# base-1.net
KiCad netlist of a schematic drawn in EAGLE
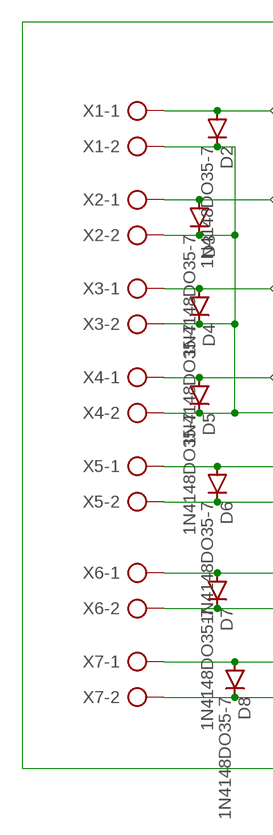
[diagram p0: schematic, sheet 1, part 1 of 2]
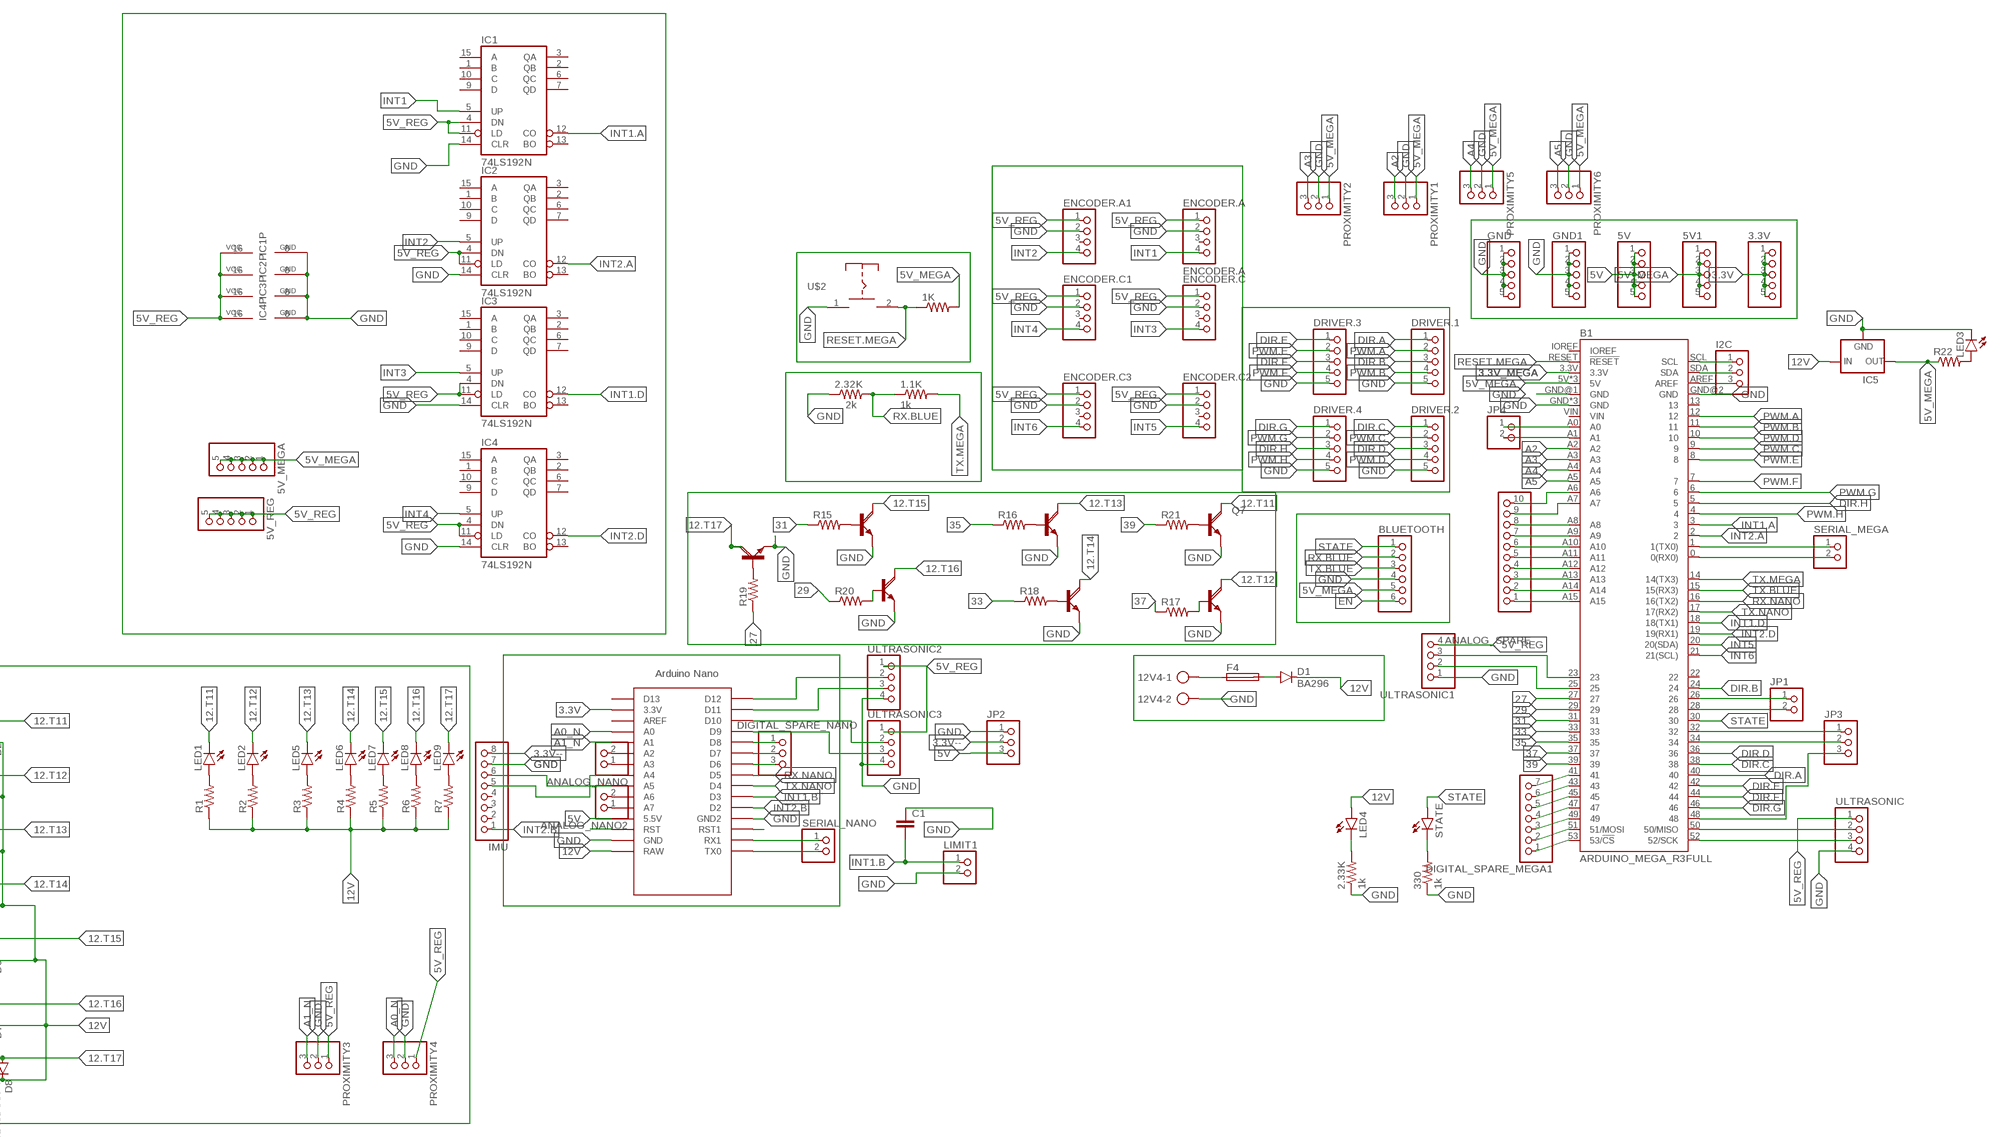
[diagram p1: schematic, sheet 1, part 2 of 2]

(export (version "E")
  (design (tool "Eeschema 10.0.6"))
  (components
    (comp (ref "1.1K")
      (value "1k")
      (footprint "eagle-import:0204_5")
      (libsource (lib "eagle-import") (part "R-US_0204/5"))
    )
    (comp (ref "1K")
      (value "R-US_0204/5")
      (footprint "eagle-import:0204_5")
      (libsource (lib "eagle-import") (part "R-US_0204/5"))
    )
    (comp (ref "2.32K")
      (value "2k")
      (footprint "eagle-import:0204_5")
      (libsource (lib "eagle-import") (part "R-US_0204/5"))
    )
    (comp (ref "2.33K")
      (value "1k")
      (footprint "eagle-import:0207_10")
      (libsource (lib "eagle-import") (part "R-US_0207/10"))
    )
    (comp (ref "3.3V")
      (value "PINHD-1X5")
      (footprint "eagle-import:1X05")
      (libsource (lib "eagle-import") (part "PINHD-1X5"))
    )
    (comp (ref "5V")
      (value "PINHD-1X5")
      (footprint "eagle-import:1X05")
      (libsource (lib "eagle-import") (part "PINHD-1X5"))
    )
    (comp (ref "5V1")
      (value "PINHD-1X5")
      (footprint "eagle-import:1X05")
      (libsource (lib "eagle-import") (part "PINHD-1X5"))
    )
    (comp (ref "5V_MEGA")
      (value "PINHD-1X5")
      (footprint "eagle-import:1X05")
      (libsource (lib "eagle-import") (part "PINHD-1X5"))
    )
    (comp (ref "5V_REG")
      (value "PINHD-1X5")
      (footprint "eagle-import:1X05")
      (libsource (lib "eagle-import") (part "PINHD-1X5"))
    )
    (comp (ref "12V4")
      (value "W237-113")
      (footprint "eagle-import:W237-113")
      (libsource (lib "eagle-import") (part "W237-113"))
    )
    (comp (ref "330")
      (value "1k")
      (footprint "eagle-import:0204_5")
      (libsource (lib "eagle-import") (part "R-US_0204/5"))
    )
    (comp (ref "ANALOG_NANO")
      (value "PINHD-1X2")
      (footprint "eagle-import:1X02")
      (libsource (lib "eagle-import") (part "PINHD-1X2"))
    )
    (comp (ref "ANALOG_NANO2")
      (value "PINHD-1X2")
      (footprint "eagle-import:1X02")
      (libsource (lib "eagle-import") (part "PINHD-1X2"))
    )
    (comp (ref "ANALOG_SPARE")
      (value "PINHD-1X10")
      (footprint "eagle-import:1X10")
      (libsource (lib "eagle-import") (part "PINHD-1X10"))
    )
    (comp (ref "B1")
      (value "ARDUINO_MEGA_R3FULL")
      (footprint "eagle-import:ARDUINO_MEGA_NO_SILK")
      (libsource (lib "eagle-import") (part "ARDUINO_MEGA_R3FULL"))
    )
    (comp (ref "BLUETOOTH")
      (value "PINHD-1X6")
      (footprint "eagle-import:1X06")
      (libsource (lib "eagle-import") (part "PINHD-1X6"))
    )
    (comp (ref "C1")
      (value "C-EU025-025X050")
      (footprint "eagle-import:C025-025X050")
      (libsource (lib "eagle-import") (part "C-EU025-025X050"))
    )
    (comp (ref "D1")
      (value "BA296")
      (footprint "eagle-import:P2-15")
      (libsource (lib "eagle-import") (part "BA296"))
    )
    (comp (ref "D2")
      (value "1N4148DO35-7")
      (footprint "eagle-import:DO35-7")
      (libsource (lib "eagle-import") (part "1N4148DO35-7"))
    )
    (comp (ref "D3")
      (value "1N4148DO35-7")
      (footprint "eagle-import:DO35-7")
      (libsource (lib "eagle-import") (part "1N4148DO35-7"))
    )
    (comp (ref "D4")
      (value "1N4148DO35-7")
      (footprint "eagle-import:DO35-7")
      (libsource (lib "eagle-import") (part "1N4148DO35-7"))
    )
    (comp (ref "D5")
      (value "1N4148DO35-7")
      (footprint "eagle-import:DO35-7")
      (libsource (lib "eagle-import") (part "1N4148DO35-7"))
    )
    (comp (ref "D6")
      (value "1N4148DO35-7")
      (footprint "eagle-import:DO35-7")
      (libsource (lib "eagle-import") (part "1N4148DO35-7"))
    )
    (comp (ref "D7")
      (value "1N4148DO35-7")
      (footprint "eagle-import:DO35-7")
      (libsource (lib "eagle-import") (part "1N4148DO35-7"))
    )
    (comp (ref "D8")
      (value "1N4148DO35-7")
      (footprint "eagle-import:DO35-7")
      (libsource (lib "eagle-import") (part "1N4148DO35-7"))
    )
    (comp (ref "DIGITAL_SPARE_MEGA1")
      (value "PINHD-1X7")
      (footprint "eagle-import:1X07")
      (libsource (lib "eagle-import") (part "PINHD-1X7"))
    )
    (comp (ref "DIGITAL_SPARE_NANO")
      (value "PINHD-1X3")
      (footprint "eagle-import:1X03")
      (libsource (lib "eagle-import") (part "PINHD-1X3"))
    )
    (comp (ref "DRIVER.1")
      (value "PINHD-1X5")
      (footprint "eagle-import:1X05")
      (libsource (lib "eagle-import") (part "PINHD-1X5"))
    )
    (comp (ref "DRIVER.2")
      (value "PINHD-1X5")
      (footprint "eagle-import:1X05")
      (libsource (lib "eagle-import") (part "PINHD-1X5"))
    )
    (comp (ref "DRIVER.3")
      (value "PINHD-1X5")
      (footprint "eagle-import:1X05")
      (libsource (lib "eagle-import") (part "PINHD-1X5"))
    )
    (comp (ref "DRIVER.4")
      (value "PINHD-1X5")
      (footprint "eagle-import:1X05")
      (libsource (lib "eagle-import") (part "PINHD-1X5"))
    )
    (comp (ref "ENCODER.A")
      (value "ENCODER.A")
      (footprint "eagle-import:1X04")
      (libsource (lib "eagle-import") (part "PINHD-1X4"))
    )
    (comp (ref "ENCODER.A1")
      (value "PINHD-1X4")
      (footprint "eagle-import:1X04")
      (libsource (lib "eagle-import") (part "PINHD-1X4"))
    )
    (comp (ref "ENCODER.C")
      (value "PINHD-1X4")
      (footprint "eagle-import:1X04")
      (libsource (lib "eagle-import") (part "PINHD-1X4"))
    )
    (comp (ref "ENCODER.C1")
      (value "PINHD-1X4")
      (footprint "eagle-import:1X04")
      (libsource (lib "eagle-import") (part "PINHD-1X4"))
    )
    (comp (ref "ENCODER.C2")
      (value "PINHD-1X4")
      (footprint "eagle-import:1X04")
      (libsource (lib "eagle-import") (part "PINHD-1X4"))
    )
    (comp (ref "ENCODER.C3")
      (value "PINHD-1X4")
      (footprint "eagle-import:1X04")
      (libsource (lib "eagle-import") (part "PINHD-1X4"))
    )
    (comp (ref "F4")
      (value "SH22,5A")
      (footprint "eagle-import:SH22,5A")
      (fields (field (name "MPN") "0031.7701.11"))
      (libsource (lib "eagle-import") (part "SH22,5A"))
    )
    (comp (ref "GND")
      (value "PINHD-1X5")
      (footprint "eagle-import:1X05")
      (libsource (lib "eagle-import") (part "PINHD-1X5"))
    )
    (comp (ref "GND1")
      (value "PINHD-1X5")
      (footprint "eagle-import:1X05")
      (libsource (lib "eagle-import") (part "PINHD-1X5"))
    )
    (comp (ref "I2C")
      (value "PINHD-1X3")
      (footprint "eagle-import:1X03")
      (libsource (lib "eagle-import") (part "PINHD-1X3"))
    )
    (comp (ref "IC1")
      (value "74LS192N")
      (footprint "eagle-import:DIL16")
      (libsource (lib "eagle-import") (part "74192NLS"))
    )
    (comp (ref "IC2")
      (value "74LS192N")
      (footprint "eagle-import:DIL16")
      (libsource (lib "eagle-import") (part "74192NLS"))
    )
    (comp (ref "IC3")
      (value "74LS192N")
      (footprint "eagle-import:DIL16")
      (libsource (lib "eagle-import") (part "74192NLS"))
    )
    (comp (ref "IC4")
      (value "74LS192N")
      (footprint "eagle-import:DIL16")
      (libsource (lib "eagle-import") (part "74192NLS"))
    )
    (comp (ref "IC5")
      (value "79XX-TO3")
      (footprint "eagle-import:TO3-79")
      (libsource (lib "eagle-import") (part "79XX-TO3"))
    )
    (comp (ref "IMU")
      (value "PINHD-1X8")
      (footprint "eagle-import:1X08")
      (libsource (lib "eagle-import") (part "PINHD-1X8"))
    )
    (comp (ref "JP1")
      (value "PINHD-1X2")
      (footprint "eagle-import:1X02")
      (libsource (lib "eagle-import") (part "PINHD-1X2"))
    )
    (comp (ref "JP2")
      (value "PINHD-1X3")
      (footprint "eagle-import:1X03")
      (libsource (lib "eagle-import") (part "PINHD-1X3"))
    )
    (comp (ref "JP3")
      (value "PINHD-1X3")
      (footprint "eagle-import:1X03")
      (libsource (lib "eagle-import") (part "PINHD-1X3"))
    )
    (comp (ref "JP4")
      (value "PINHD-1X2")
      (footprint "eagle-import:1X02")
      (libsource (lib "eagle-import") (part "PINHD-1X2"))
    )
    (comp (ref "LED1")
      (value "LED3MM")
      (footprint "eagle-import:LED3MM")
      (libsource (lib "eagle-import") (part "LED3MM"))
    )
    (comp (ref "LED2")
      (value "LED3MM")
      (footprint "eagle-import:LED3MM")
      (libsource (lib "eagle-import") (part "LED3MM"))
    )
    (comp (ref "LED3")
      (value "LED3MM")
      (footprint "eagle-import:LED3MM")
      (libsource (lib "eagle-import") (part "LED3MM"))
    )
    (comp (ref "LED4")
      (value "LED5MM")
      (footprint "eagle-import:LED5MM")
      (libsource (lib "eagle-import") (part "LED5MM"))
    )
    (comp (ref "LED5")
      (value "LED3MM")
      (footprint "eagle-import:LED3MM")
      (libsource (lib "eagle-import") (part "LED3MM"))
    )
    (comp (ref "LED6")
      (value "LED3MM")
      (footprint "eagle-import:LED3MM")
      (libsource (lib "eagle-import") (part "LED3MM"))
    )
    (comp (ref "LED7")
      (value "LED3MM")
      (footprint "eagle-import:LED3MM")
      (libsource (lib "eagle-import") (part "LED3MM"))
    )
    (comp (ref "LED8")
      (value "LED3MM")
      (footprint "eagle-import:LED3MM")
      (libsource (lib "eagle-import") (part "LED3MM"))
    )
    (comp (ref "LED9")
      (value "LED3MM")
      (footprint "eagle-import:LED3MM")
      (libsource (lib "eagle-import") (part "LED3MM"))
    )
    (comp (ref "LIMIT1")
      (value "PINHD-1X2")
      (footprint "eagle-import:1X02")
      (libsource (lib "eagle-import") (part "PINHD-1X2"))
    )
    (comp (ref "PROXIMITY1")
      (value "PINHD-1X3")
      (footprint "eagle-import:1X03")
      (libsource (lib "eagle-import") (part "PINHD-1X3"))
    )
    (comp (ref "PROXIMITY2")
      (value "PINHD-1X3")
      (footprint "eagle-import:1X03")
      (libsource (lib "eagle-import") (part "PINHD-1X3"))
    )
    (comp (ref "PROXIMITY3")
      (value "PINHD-1X3")
      (footprint "eagle-import:1X03")
      (libsource (lib "eagle-import") (part "PINHD-1X3"))
    )
    (comp (ref "PROXIMITY4")
      (value "PINHD-1X3")
      (footprint "eagle-import:1X03")
      (libsource (lib "eagle-import") (part "PINHD-1X3"))
    )
    (comp (ref "PROXIMITY5")
      (value "PINHD-1X3")
      (footprint "eagle-import:1X03")
      (libsource (lib "eagle-import") (part "PINHD-1X3"))
    )
    (comp (ref "PROXIMITY6")
      (value "PINHD-1X3")
      (footprint "eagle-import:1X03")
      (libsource (lib "eagle-import") (part "PINHD-1X3"))
    )
    (comp (ref "Q1")
      (value "TIP120")
      (footprint "eagle-import:TO220AV")
      (libsource (lib "eagle-import") (part "TIP120"))
    )
    (comp (ref "Q2")
      (value "TIP120")
      (footprint "eagle-import:TO220AV")
      (libsource (lib "eagle-import") (part "TIP120"))
    )
    (comp (ref "Q3")
      (value "TIP120")
      (footprint "eagle-import:TO220AV")
      (libsource (lib "eagle-import") (part "TIP120"))
    )
    (comp (ref "Q4")
      (value "TIP120")
      (footprint "eagle-import:TO220AV")
      (libsource (lib "eagle-import") (part "TIP120"))
    )
    (comp (ref "Q5")
      (value "TIP120")
      (footprint "eagle-import:TO220AV")
      (libsource (lib "eagle-import") (part "TIP120"))
    )
    (comp (ref "Q6")
      (value "TIP120")
      (footprint "eagle-import:TO220AV")
      (libsource (lib "eagle-import") (part "TIP120"))
    )
    (comp (ref "Q7")
      (value "TIP120")
      (footprint "eagle-import:TO220AV")
      (libsource (lib "eagle-import") (part "TIP120"))
    )
    (comp (ref "R1")
      (value "R-US_0204/5")
      (footprint "eagle-import:0204_5")
      (libsource (lib "eagle-import") (part "R-US_0204/5"))
    )
    (comp (ref "R2")
      (value "R-US_0204/5")
      (footprint "eagle-import:0204_5")
      (libsource (lib "eagle-import") (part "R-US_0204/5"))
    )
    (comp (ref "R3")
      (value "R-US_0204/5")
      (footprint "eagle-import:0204_5")
      (libsource (lib "eagle-import") (part "R-US_0204/5"))
    )
    (comp (ref "R4")
      (value "R-US_0204/5")
      (footprint "eagle-import:0204_5")
      (libsource (lib "eagle-import") (part "R-US_0204/5"))
    )
    (comp (ref "R5")
      (value "R-US_0204/5")
      (footprint "eagle-import:0204_5")
      (libsource (lib "eagle-import") (part "R-US_0204/5"))
    )
    (comp (ref "R6")
      (value "R-US_0204/5")
      (footprint "eagle-import:0204_5")
      (libsource (lib "eagle-import") (part "R-US_0204/5"))
    )
    (comp (ref "R7")
      (value "R-US_0204/5")
      (footprint "eagle-import:0204_5")
      (libsource (lib "eagle-import") (part "R-US_0204/5"))
    )
    (comp (ref "R15")
      (value "R-US_0207/10")
      (footprint "eagle-import:0207_10")
      (libsource (lib "eagle-import") (part "R-US_0207/10"))
    )
    (comp (ref "R16")
      (value "R-US_0204/7")
      (footprint "eagle-import:0204_7")
      (libsource (lib "eagle-import") (part "R-US_0204/7"))
    )
    (comp (ref "R17")
      (value "R-US_0204/7")
      (footprint "eagle-import:0204_7")
      (libsource (lib "eagle-import") (part "R-US_0204/7"))
    )
    (comp (ref "R18")
      (value "R-US_0204/7")
      (footprint "eagle-import:0204_7")
      (libsource (lib "eagle-import") (part "R-US_0204/7"))
    )
    (comp (ref "R19")
      (value "R-US_0204/7")
      (footprint "eagle-import:0204_7")
      (libsource (lib "eagle-import") (part "R-US_0204/7"))
    )
    (comp (ref "R20")
      (value "R-US_0204/7")
      (footprint "eagle-import:0204_7")
      (libsource (lib "eagle-import") (part "R-US_0204/7"))
    )
    (comp (ref "R21")
      (value "R-US_0204/5")
      (footprint "eagle-import:0204_5")
      (libsource (lib "eagle-import") (part "R-US_0204/5"))
    )
    (comp (ref "R22")
      (value "R-US_0204/5")
      (footprint "eagle-import:0204_5")
      (libsource (lib "eagle-import") (part "R-US_0204/5"))
    )
    (comp (ref "SERIAL_MEGA")
      (value "PINHD-1X2")
      (footprint "eagle-import:1X02")
      (libsource (lib "eagle-import") (part "PINHD-1X2"))
    )
    (comp (ref "SERIAL_NANO")
      (value "PINHD-1X2")
      (footprint "eagle-import:1X02")
      (libsource (lib "eagle-import") (part "PINHD-1X2"))
    )
    (comp (ref "STATE")
      (value "LED3MM")
      (footprint "eagle-import:LED3MM")
      (libsource (lib "eagle-import") (part "LED3MM"))
    )
    (comp (ref "U$1")
      (value "NANO")
      (footprint "eagle-import:NANO")
      (libsource (lib "eagle-import") (part "NANO"))
    )
    (comp (ref "U$2")
      (value "PUSHBOTTON")
      (footprint "eagle-import:PUSHBOTTON")
      (libsource (lib "eagle-import") (part "PUSHBOTTON"))
    )
    (comp (ref "ULTRASONIC")
      (value "PINHD-1X4")
      (footprint "eagle-import:1X04")
      (libsource (lib "eagle-import") (part "PINHD-1X4"))
    )
    (comp (ref "ULTRASONIC1")
      (value "PINHD-1X4")
      (footprint "eagle-import:1X04")
      (libsource (lib "eagle-import") (part "PINHD-1X4"))
    )
    (comp (ref "ULTRASONIC2")
      (value "PINHD-1X4")
      (footprint "eagle-import:1X04")
      (libsource (lib "eagle-import") (part "PINHD-1X4"))
    )
    (comp (ref "ULTRASONIC3")
      (value "PINHD-1X4")
      (footprint "eagle-import:1X04")
      (libsource (lib "eagle-import") (part "PINHD-1X4"))
    )
    (comp (ref "X1")
      (value "AK300/2")
      (footprint "eagle-import:AK300_2")
      (libsource (lib "eagle-import") (part "AK300/2"))
    )
    (comp (ref "X2")
      (value "AK300/2")
      (footprint "eagle-import:AK300_2")
      (libsource (lib "eagle-import") (part "AK300/2"))
    )
    (comp (ref "X3")
      (value "AK300/2")
      (footprint "eagle-import:AK300_2")
      (libsource (lib "eagle-import") (part "AK300/2"))
    )
    (comp (ref "X4")
      (value "AK300/2")
      (footprint "eagle-import:AK300_2")
      (libsource (lib "eagle-import") (part "AK300/2"))
    )
    (comp (ref "X5")
      (value "AK300/2")
      (footprint "eagle-import:AK300_2")
      (libsource (lib "eagle-import") (part "AK300/2"))
    )
    (comp (ref "X6")
      (value "AK300/2")
      (footprint "eagle-import:AK300_2")
      (libsource (lib "eagle-import") (part "AK300/2"))
    )
    (comp (ref "X7")
      (value "AK300/2")
      (footprint "eagle-import:AK300_2")
      (libsource (lib "eagle-import") (part "AK300/2"))
    )
  )
  (nets
    (net (code "1") (name "3.3V") (class "Default")
      (node (ref "3.3V") (pin "1") (pinfunction "1_1") (pintype "passive"))
      (node (ref "3.3V") (pin "2") (pinfunction "2_2") (pintype "passive"))
      (node (ref "3.3V") (pin "3") (pinfunction "3_3") (pintype "passive"))
      (node (ref "3.3V") (pin "4") (pinfunction "4_4") (pintype "passive"))
      (node (ref "3.3V") (pin "5") (pinfunction "5_5") (pintype "passive"))
      (node (ref "U$1") (pin "3.3V") (pinfunction "3.3V_3.3V") (pintype "bidirectional"))
    )
    (net (code "2") (name "3.3V--") (class "Default")
      (node (ref "IMU") (pin "8") (pinfunction "8_8") (pintype "passive"))
      (node (ref "JP2") (pin "2") (pinfunction "2_2") (pintype "passive"))
    )
    (net (code "3") (name "3.3V_MEGA") (class "Default")
      (node (ref "B1") (pin "3.3V") (pinfunction "3.3V_3.3V") (pintype "bidirectional"))
    )
    (net (code "4") (name "5V") (class "Default")
      (node (ref "5V") (pin "1") (pinfunction "1_1") (pintype "passive"))
      (node (ref "5V") (pin "2") (pinfunction "2_2") (pintype "passive"))
      (node (ref "5V") (pin "3") (pinfunction "3_3") (pintype "passive"))
      (node (ref "5V") (pin "4") (pinfunction "4_4") (pintype "passive"))
      (node (ref "5V") (pin "5") (pinfunction "5_5") (pintype "passive"))
      (node (ref "JP2") (pin "3") (pinfunction "3_3") (pintype "passive"))
      (node (ref "U$1") (pin "5V") (pinfunction "5.5V_5V") (pintype "bidirectional"))
    )
    (net (code "5") (name "5V_MEGA") (class "Default")
      (node (ref "1K") (pin "2") (pinfunction "2_2") (pintype "passive"))
      (node (ref "5V1") (pin "1") (pinfunction "1_1") (pintype "passive"))
      (node (ref "5V1") (pin "2") (pinfunction "2_2") (pintype "passive"))
      (node (ref "5V1") (pin "3") (pinfunction "3_3") (pintype "passive"))
      (node (ref "5V1") (pin "4") (pinfunction "4_4") (pintype "passive"))
      (node (ref "5V1") (pin "5") (pinfunction "5_5") (pintype "passive"))
      (node (ref "5V_MEGA") (pin "1") (pinfunction "1_1") (pintype "passive"))
      (node (ref "5V_MEGA") (pin "2") (pinfunction "2_2") (pintype "passive"))
      (node (ref "5V_MEGA") (pin "3") (pinfunction "3_3") (pintype "passive"))
      (node (ref "5V_MEGA") (pin "4") (pinfunction "4_4") (pintype "passive"))
      (node (ref "5V_MEGA") (pin "5") (pinfunction "5_5") (pintype "passive"))
      (node (ref "B1") (pin "5V") (pinfunction "5V_5V") (pintype "bidirectional"))
      (node (ref "B1") (pin "5V@1") (pinfunction "5V_5V@1") (pintype "bidirectional"))
      (node (ref "B1") (pin "5V@2") (pinfunction "5V_5V@2") (pintype "bidirectional"))
      (node (ref "BLUETOOTH") (pin "5") (pinfunction "5_5") (pintype "passive"))
      (node (ref "IC5") (pin "1") (pinfunction "OUT_1") (pintype "passive"))
      (node (ref "PROXIMITY1") (pin "1") (pinfunction "1_1") (pintype "passive"))
      (node (ref "PROXIMITY2") (pin "1") (pinfunction "1_1") (pintype "passive"))
      (node (ref "PROXIMITY5") (pin "1") (pinfunction "1_1") (pintype "passive"))
      (node (ref "PROXIMITY6") (pin "1") (pinfunction "1_1") (pintype "passive"))
      (node (ref "R22") (pin "1") (pinfunction "1_1") (pintype "passive"))
    )
    (net (code "6") (name "5V_REG") (class "Default")
      (node (ref "5V_REG") (pin "1") (pinfunction "1_1") (pintype "passive"))
      (node (ref "5V_REG") (pin "2") (pinfunction "2_2") (pintype "passive"))
      (node (ref "5V_REG") (pin "3") (pinfunction "3_3") (pintype "passive"))
      (node (ref "5V_REG") (pin "4") (pinfunction "4_4") (pintype "passive"))
      (node (ref "5V_REG") (pin "5") (pinfunction "5_5") (pintype "passive"))
      (node (ref "ENCODER.A") (pin "1") (pinfunction "1_1") (pintype "passive"))
      (node (ref "ENCODER.A1") (pin "1") (pinfunction "1_1") (pintype "passive"))
      (node (ref "ENCODER.C") (pin "1") (pinfunction "1_1") (pintype "passive"))
      (node (ref "ENCODER.C1") (pin "1") (pinfunction "1_1") (pintype "passive"))
      (node (ref "ENCODER.C2") (pin "1") (pinfunction "1_1") (pintype "passive"))
      (node (ref "ENCODER.C3") (pin "1") (pinfunction "1_1") (pintype "passive"))
      (node (ref "IC1") (pin "11") (pinfunction "LD_11") (pintype "input"))
      (node (ref "IC1") (pin "16") (pinfunction "VCC_16") (pintype "power_in"))
      (node (ref "IC1") (pin "4") (pinfunction "DN_4") (pintype "input"))
      (node (ref "IC2") (pin "11") (pinfunction "LD_11") (pintype "input"))
      (node (ref "IC2") (pin "16") (pinfunction "VCC_16") (pintype "power_in"))
      (node (ref "IC2") (pin "4") (pinfunction "DN_4") (pintype "input"))
      (node (ref "IC3") (pin "11") (pinfunction "LD_11") (pintype "input"))
      (node (ref "IC3") (pin "16") (pinfunction "VCC_16") (pintype "power_in"))
      (node (ref "IC3") (pin "4") (pinfunction "DN_4") (pintype "input"))
      (node (ref "IC4") (pin "11") (pinfunction "LD_11") (pintype "input"))
      (node (ref "IC4") (pin "16") (pinfunction "VCC_16") (pintype "power_in"))
      (node (ref "IC4") (pin "4") (pinfunction "DN_4") (pintype "input"))
      (node (ref "PROXIMITY3") (pin "1") (pinfunction "1_1") (pintype "passive"))
      (node (ref "PROXIMITY4") (pin "1") (pinfunction "1_1") (pintype "passive"))
      (node (ref "ULTRASONIC") (pin "1") (pinfunction "1_1") (pintype "passive"))
      (node (ref "ULTRASONIC1") (pin "4") (pinfunction "4_4") (pintype "passive"))
      (node (ref "ULTRASONIC2") (pin "1") (pinfunction "1_1") (pintype "passive"))
      (node (ref "ULTRASONIC3") (pin "1") (pinfunction "1_1") (pintype "passive"))
    )
    (net (code "7") (name "12.T11") (class "Default")
      (node (ref "D2") (pin "A") (pinfunction "A_A") (pintype "passive"))
      (node (ref "LED1") (pin "K") (pinfunction "C_K") (pintype "passive"))
      (node (ref "Q7") (pin "C") (pinfunction "C_C") (pintype "passive"))
      (node (ref "X1") (pin "1") (pinfunction "KL_1") (pintype "passive"))
    )
    (net (code "8") (name "12.T12") (class "Default")
      (node (ref "D3") (pin "A") (pinfunction "A_A") (pintype "passive"))
      (node (ref "LED2") (pin "K") (pinfunction "C_K") (pintype "passive"))
      (node (ref "Q5") (pin "C") (pinfunction "C_C") (pintype "passive"))
      (node (ref "X2") (pin "1") (pinfunction "KL_1") (pintype "passive"))
    )
    (net (code "9") (name "12.T13") (class "Default")
      (node (ref "D4") (pin "A") (pinfunction "A_A") (pintype "passive"))
      (node (ref "LED5") (pin "K") (pinfunction "C_K") (pintype "passive"))
      (node (ref "Q2") (pin "C") (pinfunction "C_C") (pintype "passive"))
      (node (ref "X3") (pin "1") (pinfunction "KL_1") (pintype "passive"))
    )
    (net (code "10") (name "12.T14") (class "Default")
      (node (ref "D5") (pin "A") (pinfunction "A_A") (pintype "passive"))
      (node (ref "LED6") (pin "K") (pinfunction "C_K") (pintype "passive"))
      (node (ref "Q4") (pin "C") (pinfunction "C_C") (pintype "passive"))
      (node (ref "X4") (pin "1") (pinfunction "KL_1") (pintype "passive"))
    )
    (net (code "11") (name "12.T15") (class "Default")
      (node (ref "D6") (pin "A") (pinfunction "A_A") (pintype "passive"))
      (node (ref "LED7") (pin "K") (pinfunction "C_K") (pintype "passive"))
      (node (ref "Q1") (pin "C") (pinfunction "C_C") (pintype "passive"))
      (node (ref "X5") (pin "1") (pinfunction "KL_1") (pintype "passive"))
    )
    (net (code "12") (name "12.T16") (class "Default")
      (node (ref "D7") (pin "A") (pinfunction "A_A") (pintype "passive"))
      (node (ref "LED8") (pin "K") (pinfunction "C_K") (pintype "passive"))
      (node (ref "Q6") (pin "C") (pinfunction "C_C") (pintype "passive"))
      (node (ref "X6") (pin "1") (pinfunction "KL_1") (pintype "passive"))
    )
    (net (code "13") (name "12.T17") (class "Default")
      (node (ref "D8") (pin "A") (pinfunction "A_A") (pintype "passive"))
      (node (ref "LED9") (pin "K") (pinfunction "C_K") (pintype "passive"))
      (node (ref "Q3") (pin "C") (pinfunction "C_C") (pintype "passive"))
      (node (ref "X7") (pin "1") (pinfunction "KL_1") (pintype "passive"))
    )
    (net (code "14") (name "12V") (class "Default")
      (node (ref "D1") (pin "C") (pinfunction "C_C") (pintype "passive"))
      (node (ref "D2") (pin "C") (pinfunction "C_C") (pintype "passive"))
      (node (ref "D3") (pin "C") (pinfunction "C_C") (pintype "passive"))
      (node (ref "D4") (pin "C") (pinfunction "C_C") (pintype "passive"))
      (node (ref "D5") (pin "C") (pinfunction "C_C") (pintype "passive"))
      (node (ref "D6") (pin "C") (pinfunction "C_C") (pintype "passive"))
      (node (ref "D7") (pin "C") (pinfunction "C_C") (pintype "passive"))
      (node (ref "D8") (pin "C") (pinfunction "C_C") (pintype "passive"))
      (node (ref "IC5") (pin "3") (pinfunction "IN_3") (pintype "input"))
      (node (ref "LED4") (pin "A") (pinfunction "A_A") (pintype "passive"))
      (node (ref "R1") (pin "1") (pinfunction "1_1") (pintype "passive"))
      (node (ref "R2") (pin "1") (pinfunction "1_1") (pintype "passive"))
      (node (ref "R3") (pin "1") (pinfunction "1_1") (pintype "passive"))
      (node (ref "R4") (pin "1") (pinfunction "1_1") (pintype "passive"))
      (node (ref "R5") (pin "1") (pinfunction "1_1") (pintype "passive"))
      (node (ref "R6") (pin "1") (pinfunction "1_1") (pintype "passive"))
      (node (ref "R7") (pin "1") (pinfunction "1_1") (pintype "passive"))
      (node (ref "U$1") (pin "RAW") (pinfunction "RAW_RAW") (pintype "bidirectional"))
      (node (ref "X1") (pin "2") (pinfunction "KL_2") (pintype "passive"))
      (node (ref "X2") (pin "2") (pinfunction "KL_2") (pintype "passive"))
      (node (ref "X3") (pin "2") (pinfunction "KL_2") (pintype "passive"))
      (node (ref "X4") (pin "2") (pinfunction "KL_2") (pintype "passive"))
      (node (ref "X5") (pin "2") (pinfunction "KL_2") (pintype "passive"))
      (node (ref "X6") (pin "2") (pinfunction "KL_2") (pintype "passive"))
      (node (ref "X7") (pin "2") (pinfunction "KL_2") (pintype "passive"))
    )
    (net (code "15") (name "27") (class "Default")
      (node (ref "B1") (pin "27") (pinfunction "27_27") (pintype "bidirectional"))
      (node (ref "R19") (pin "1") (pinfunction "1_1") (pintype "passive"))
    )
    (net (code "16") (name "29") (class "Default")
      (node (ref "B1") (pin "29") (pinfunction "29_29") (pintype "bidirectional"))
      (node (ref "R20") (pin "1") (pinfunction "1_1") (pintype "passive"))
    )
    (net (code "17") (name "31") (class "Default")
      (node (ref "B1") (pin "31") (pinfunction "31_31") (pintype "bidirectional"))
      (node (ref "R15") (pin "1") (pinfunction "1_1") (pintype "passive"))
    )
    (net (code "18") (name "33") (class "Default")
      (node (ref "B1") (pin "33") (pinfunction "33_33") (pintype "bidirectional"))
      (node (ref "R18") (pin "1") (pinfunction "1_1") (pintype "passive"))
    )
    (net (code "19") (name "35") (class "Default")
      (node (ref "B1") (pin "35") (pinfunction "35_35") (pintype "bidirectional"))
      (node (ref "R16") (pin "1") (pinfunction "1_1") (pintype "passive"))
    )
    (net (code "20") (name "37") (class "Default")
      (node (ref "B1") (pin "37") (pinfunction "37_37") (pintype "bidirectional"))
      (node (ref "R17") (pin "1") (pinfunction "1_1") (pintype "passive"))
    )
    (net (code "21") (name "39") (class "Default")
      (node (ref "B1") (pin "39") (pinfunction "39_39") (pintype "bidirectional"))
      (node (ref "R21") (pin "1") (pinfunction "1_1") (pintype "passive"))
    )
    (net (code "22") (name "A0_N") (class "Default")
      (node (ref "PROXIMITY4") (pin "3") (pinfunction "3_3") (pintype "passive"))
      (node (ref "U$1") (pin "A0") (pinfunction "A0_A0") (pintype "bidirectional"))
    )
    (net (code "23") (name "A1_N") (class "Default")
      (node (ref "PROXIMITY3") (pin "3") (pinfunction "3_3") (pintype "passive"))
      (node (ref "U$1") (pin "A1") (pinfunction "A1_A1") (pintype "bidirectional"))
    )
    (net (code "24") (name "A2") (class "Default")
      (node (ref "B1") (pin "A2") (pinfunction "A2_A2") (pintype "bidirectional"))
      (node (ref "PROXIMITY1") (pin "3") (pinfunction "3_3") (pintype "passive"))
    )
    (net (code "25") (name "A3") (class "Default")
      (node (ref "B1") (pin "A3") (pinfunction "A3_A3") (pintype "bidirectional"))
      (node (ref "PROXIMITY2") (pin "3") (pinfunction "3_3") (pintype "passive"))
    )
    (net (code "26") (name "A4") (class "Default")
      (node (ref "B1") (pin "A4") (pinfunction "A4_A4") (pintype "bidirectional"))
      (node (ref "PROXIMITY5") (pin "3") (pinfunction "3_3") (pintype "passive"))
    )
    (net (code "27") (name "A5") (class "Default")
      (node (ref "B1") (pin "A5") (pinfunction "A5_A5") (pintype "bidirectional"))
      (node (ref "PROXIMITY6") (pin "3") (pinfunction "3_3") (pintype "passive"))
    )
    (net (code "28") (name "DIR.A") (class "Default")
      (node (ref "B1") (pin "40") (pinfunction "40_40") (pintype "bidirectional"))
      (node (ref "DRIVER.1") (pin "1") (pinfunction "1_1") (pintype "passive"))
    )
    (net (code "29") (name "DIR.B") (class "Default")
      (node (ref "B1") (pin "24") (pinfunction "24_24") (pintype "bidirectional"))
      (node (ref "DRIVER.1") (pin "3") (pinfunction "3_3") (pintype "passive"))
    )
    (net (code "30") (name "DIR.C") (class "Default")
      (node (ref "B1") (pin "38") (pinfunction "38_38") (pintype "bidirectional"))
      (node (ref "DRIVER.2") (pin "1") (pinfunction "1_1") (pintype "passive"))
    )
    (net (code "31") (name "DIR.D") (class "Default")
      (node (ref "B1") (pin "36") (pinfunction "36_36") (pintype "bidirectional"))
      (node (ref "DRIVER.2") (pin "3") (pinfunction "3_3") (pintype "passive"))
    )
    (net (code "32") (name "DIR.E") (class "Default")
      (node (ref "B1") (pin "42") (pinfunction "42_42") (pintype "bidirectional"))
      (node (ref "DRIVER.3") (pin "1") (pinfunction "1_1") (pintype "passive"))
    )
    (net (code "33") (name "DIR.F") (class "Default")
      (node (ref "B1") (pin "44") (pinfunction "44_44") (pintype "bidirectional"))
      (node (ref "DRIVER.3") (pin "3") (pinfunction "3_3") (pintype "passive"))
    )
    (net (code "34") (name "DIR.G") (class "Default")
      (node (ref "B1") (pin "46") (pinfunction "46_46") (pintype "bidirectional"))
      (node (ref "DRIVER.4") (pin "1") (pinfunction "1_1") (pintype "passive"))
    )
    (net (code "35") (name "DIR.H") (class "Default")
      (node (ref "B1") (pin "5") (pinfunction "5_5") (pintype "bidirectional"))
      (node (ref "DRIVER.4") (pin "3") (pinfunction "3_3") (pintype "passive"))
    )
    (net (code "36") (name "EN") (class "Default")
      (node (ref "BLUETOOTH") (pin "6") (pinfunction "6_6") (pintype "passive"))
    )
    (net (code "37") (name "GND") (class "Default")
      (node (ref "12V4") (pin "2") (pinfunction "KL_2") (pintype "passive"))
      (node (ref "2.32K") (pin "1") (pinfunction "1_1") (pintype "passive"))
      (node (ref "2.33K") (pin "1") (pinfunction "1_1") (pintype "passive"))
      (node (ref "330") (pin "1") (pinfunction "1_1") (pintype "passive"))
      (node (ref "B1") (pin "GND") (pinfunction "GND_GND") (pintype "bidirectional"))
      (node (ref "B1") (pin "GND@1") (pinfunction "GND_GND@1") (pintype "bidirectional"))
      (node (ref "B1") (pin "GND@2") (pinfunction "GND_GND@2") (pintype "bidirectional"))
      (node (ref "B1") (pin "GND@3") (pinfunction "GND_GND@3") (pintype "bidirectional"))
      (node (ref "B1") (pin "GND@4") (pinfunction "GND_GND@4") (pintype "bidirectional"))
      (node (ref "BLUETOOTH") (pin "4") (pinfunction "4_4") (pintype "passive"))
      (node (ref "C1") (pin "1") (pinfunction "1_1") (pintype "passive"))
      (node (ref "DRIVER.1") (pin "5") (pinfunction "5_5") (pintype "passive"))
      (node (ref "DRIVER.2") (pin "5") (pinfunction "5_5") (pintype "passive"))
      (node (ref "DRIVER.3") (pin "5") (pinfunction "5_5") (pintype "passive"))
      (node (ref "DRIVER.4") (pin "5") (pinfunction "5_5") (pintype "passive"))
      (node (ref "ENCODER.A") (pin "2") (pinfunction "2_2") (pintype "passive"))
      (node (ref "ENCODER.A1") (pin "2") (pinfunction "2_2") (pintype "passive"))
      (node (ref "ENCODER.C") (pin "2") (pinfunction "2_2") (pintype "passive"))
      (node (ref "ENCODER.C1") (pin "2") (pinfunction "2_2") (pintype "passive"))
      (node (ref "ENCODER.C2") (pin "2") (pinfunction "2_2") (pintype "passive"))
      (node (ref "ENCODER.C3") (pin "2") (pinfunction "2_2") (pintype "passive"))
      (node (ref "GND") (pin "1") (pinfunction "1_1") (pintype "passive"))
      (node (ref "GND") (pin "2") (pinfunction "2_2") (pintype "passive"))
      (node (ref "GND") (pin "3") (pinfunction "3_3") (pintype "passive"))
      (node (ref "GND") (pin "4") (pinfunction "4_4") (pintype "passive"))
      (node (ref "GND") (pin "5") (pinfunction "5_5") (pintype "passive"))
      (node (ref "GND1") (pin "1") (pinfunction "1_1") (pintype "passive"))
      (node (ref "GND1") (pin "2") (pinfunction "2_2") (pintype "passive"))
      (node (ref "GND1") (pin "3") (pinfunction "3_3") (pintype "passive"))
      (node (ref "GND1") (pin "4") (pinfunction "4_4") (pintype "passive"))
      (node (ref "GND1") (pin "5") (pinfunction "5_5") (pintype "passive"))
      (node (ref "IC1") (pin "14") (pinfunction "CLR_14") (pintype "input"))
      (node (ref "IC1") (pin "8") (pinfunction "GND_8") (pintype "power_in"))
      (node (ref "IC2") (pin "14") (pinfunction "CLR_14") (pintype "input"))
      (node (ref "IC2") (pin "8") (pinfunction "GND_8") (pintype "power_in"))
      (node (ref "IC3") (pin "14") (pinfunction "CLR_14") (pintype "input"))
      (node (ref "IC3") (pin "8") (pinfunction "GND_8") (pintype "power_in"))
      (node (ref "IC4") (pin "14") (pinfunction "CLR_14") (pintype "input"))
      (node (ref "IC4") (pin "8") (pinfunction "GND_8") (pintype "power_in"))
      (node (ref "IC5") (pin "2") (pinfunction "GND_2") (pintype "input"))
      (node (ref "IMU") (pin "7") (pinfunction "7_7") (pintype "passive"))
      (node (ref "JP2") (pin "1") (pinfunction "1_1") (pintype "passive"))
      (node (ref "LED3") (pin "K") (pinfunction "C_K") (pintype "passive"))
      (node (ref "LIMIT1") (pin "2") (pinfunction "2_2") (pintype "passive"))
      (node (ref "PROXIMITY1") (pin "2") (pinfunction "2_2") (pintype "passive"))
      (node (ref "PROXIMITY2") (pin "2") (pinfunction "2_2") (pintype "passive"))
      (node (ref "PROXIMITY3") (pin "2") (pinfunction "2_2") (pintype "passive"))
      (node (ref "PROXIMITY4") (pin "2") (pinfunction "2_2") (pintype "passive"))
      (node (ref "PROXIMITY5") (pin "2") (pinfunction "2_2") (pintype "passive"))
      (node (ref "PROXIMITY6") (pin "2") (pinfunction "2_2") (pintype "passive"))
      (node (ref "Q1") (pin "E") (pinfunction "E_E") (pintype "passive"))
      (node (ref "Q2") (pin "E") (pinfunction "E_E") (pintype "passive"))
      (node (ref "Q3") (pin "E") (pinfunction "E_E") (pintype "passive"))
      (node (ref "Q4") (pin "E") (pinfunction "E_E") (pintype "passive"))
      (node (ref "Q5") (pin "E") (pinfunction "E_E") (pintype "passive"))
      (node (ref "Q6") (pin "E") (pinfunction "E_E") (pintype "passive"))
      (node (ref "Q7") (pin "E") (pinfunction "E_E") (pintype "passive"))
      (node (ref "U$1") (pin "GND") (pinfunction "GND_GND") (pintype "bidirectional"))
      (node (ref "U$1") (pin "GND1") (pinfunction "GND2_GND1") (pintype "bidirectional"))
      (node (ref "U$2") (pin "1") (pinfunction "1_1") (pintype "bidirectional"))
      (node (ref "ULTRASONIC") (pin "4") (pinfunction "4_4") (pintype "passive"))
      (node (ref "ULTRASONIC1") (pin "1") (pinfunction "1_1") (pintype "passive"))
      (node (ref "ULTRASONIC2") (pin "4") (pinfunction "4_4") (pintype "passive"))
      (node (ref "ULTRASONIC3") (pin "4") (pinfunction "4_4") (pintype "passive"))
    )
    (net (code "38") (name "INT1") (class "Default")
      (node (ref "ENCODER.A") (pin "4") (pinfunction "4_4") (pintype "passive"))
      (node (ref "IC1") (pin "5") (pinfunction "UP_5") (pintype "input"))
    )
    (net (code "39") (name "INT1.A") (class "Default")
      (node (ref "B1") (pin "3") (pinfunction "3_3") (pintype "bidirectional"))
      (node (ref "IC1") (pin "12") (pinfunction "CO_12") (pintype "output"))
    )
    (net (code "40") (name "INT1.B") (class "Default")
      (node (ref "C1") (pin "2") (pinfunction "2_2") (pintype "passive"))
      (node (ref "LIMIT1") (pin "1") (pinfunction "1_1") (pintype "passive"))
      (node (ref "U$1") (pin "D3") (pinfunction "D3_D3") (pintype "bidirectional"))
    )
    (net (code "41") (name "INT1.D") (class "Default")
      (node (ref "B1") (pin "18") (pinfunction "18(TX1)_18") (pintype "bidirectional"))
      (node (ref "IC3") (pin "12") (pinfunction "CO_12") (pintype "output"))
    )
    (net (code "42") (name "INT2") (class "Default")
      (node (ref "ENCODER.A1") (pin "4") (pinfunction "4_4") (pintype "passive"))
      (node (ref "IC2") (pin "5") (pinfunction "UP_5") (pintype "input"))
    )
    (net (code "43") (name "INT2.A") (class "Default")
      (node (ref "B1") (pin "2") (pinfunction "2_2") (pintype "bidirectional"))
      (node (ref "IC2") (pin "12") (pinfunction "CO_12") (pintype "output"))
    )
    (net (code "44") (name "INT2.B") (class "Default")
      (node (ref "IMU") (pin "1") (pinfunction "1_1") (pintype "passive"))
      (node (ref "U$1") (pin "D2") (pinfunction "D2_D2") (pintype "bidirectional"))
    )
    (net (code "45") (name "INT2.D") (class "Default")
      (node (ref "B1") (pin "19") (pinfunction "19(RX1)_19") (pintype "bidirectional"))
      (node (ref "IC4") (pin "12") (pinfunction "CO_12") (pintype "output"))
    )
    (net (code "46") (name "INT3") (class "Default")
      (node (ref "ENCODER.C") (pin "4") (pinfunction "4_4") (pintype "passive"))
      (node (ref "IC3") (pin "5") (pinfunction "UP_5") (pintype "input"))
    )
    (net (code "47") (name "INT4") (class "Default")
      (node (ref "ENCODER.C1") (pin "4") (pinfunction "4_4") (pintype "passive"))
      (node (ref "IC4") (pin "5") (pinfunction "UP_5") (pintype "input"))
    )
    (net (code "48") (name "INT5") (class "Default")
      (node (ref "B1") (pin "20") (pinfunction "20(SDA)_20") (pintype "bidirectional"))
      (node (ref "ENCODER.C2") (pin "4") (pinfunction "4_4") (pintype "passive"))
    )
    (net (code "49") (name "INT6") (class "Default")
      (node (ref "B1") (pin "21") (pinfunction "21(SCL)_21") (pintype "bidirectional"))
      (node (ref "ENCODER.C3") (pin "4") (pinfunction "4_4") (pintype "passive"))
    )
    (net (code "50") (name "Net-(12V4A-KL)") (class "Default")
      (node (ref "12V4") (pin "1") (pinfunction "KL_1") (pintype "passive"))
      (node (ref "F4") (pin "1") (pinfunction "1_1") (pintype "passive"))
    )
    (net (code "51") (name "Net-(ANALOG_NANO-Pad1)") (class "Default")
      (node (ref "ANALOG_NANO") (pin "1") (pinfunction "1_1") (pintype "passive"))
      (node (ref "U$1") (pin "A3") (pinfunction "A3_A3") (pintype "bidirectional"))
    )
    (net (code "52") (name "Net-(ANALOG_NANO-Pad2)") (class "Default")
      (node (ref "ANALOG_NANO") (pin "2") (pinfunction "2_2") (pintype "passive"))
      (node (ref "U$1") (pin "A2") (pinfunction "A2_A2") (pintype "bidirectional"))
    )
    (net (code "53") (name "Net-(ANALOG_NANO2-Pad1)") (class "Default")
      (node (ref "ANALOG_NANO2") (pin "1") (pinfunction "1_1") (pintype "passive"))
      (node (ref "U$1") (pin "A7") (pinfunction "A7_A7") (pintype "bidirectional"))
    )
    (net (code "54") (name "Net-(ANALOG_NANO2-Pad2)") (class "Default")
      (node (ref "ANALOG_NANO2") (pin "2") (pinfunction "2_2") (pintype "passive"))
      (node (ref "U$1") (pin "A6") (pinfunction "A6_A6") (pintype "bidirectional"))
    )
    (net (code "55") (name "Net-(ANALOG_SPARE-Pad1)") (class "Default")
      (node (ref "ANALOG_SPARE") (pin "1") (pinfunction "1_1") (pintype "passive"))
      (node (ref "B1") (pin "A15") (pinfunction "A15_A15") (pintype "bidirectional"))
    )
    (net (code "56") (name "Net-(ANALOG_SPARE-Pad2)") (class "Default")
      (node (ref "ANALOG_SPARE") (pin "2") (pinfunction "2_2") (pintype "passive"))
      (node (ref "B1") (pin "A14") (pinfunction "A14_A14") (pintype "bidirectional"))
    )
    (net (code "57") (name "Net-(ANALOG_SPARE-Pad3)") (class "Default")
      (node (ref "ANALOG_SPARE") (pin "3") (pinfunction "3_3") (pintype "passive"))
      (node (ref "B1") (pin "A13") (pinfunction "A13_A13") (pintype "bidirectional"))
    )
    (net (code "58") (name "Net-(ANALOG_SPARE-Pad4)") (class "Default")
      (node (ref "ANALOG_SPARE") (pin "4") (pinfunction "4_4") (pintype "passive"))
      (node (ref "B1") (pin "A12") (pinfunction "A12_A12") (pintype "bidirectional"))
    )
    (net (code "59") (name "Net-(ANALOG_SPARE-Pad5)") (class "Default")
      (node (ref "ANALOG_SPARE") (pin "5") (pinfunction "5_5") (pintype "passive"))
      (node (ref "B1") (pin "A11") (pinfunction "A11_A11") (pintype "bidirectional"))
    )
    (net (code "60") (name "Net-(ANALOG_SPARE-Pad6)") (class "Default")
      (node (ref "ANALOG_SPARE") (pin "6") (pinfunction "6_6") (pintype "passive"))
      (node (ref "B1") (pin "A10") (pinfunction "A10_A10") (pintype "bidirectional"))
    )
    (net (code "61") (name "Net-(ANALOG_SPARE-Pad7)") (class "Default")
      (node (ref "ANALOG_SPARE") (pin "7") (pinfunction "7_7") (pintype "passive"))
      (node (ref "B1") (pin "A9") (pinfunction "A9_A9") (pintype "bidirectional"))
    )
    (net (code "62") (name "Net-(ANALOG_SPARE-Pad8)") (class "Default")
      (node (ref "ANALOG_SPARE") (pin "8") (pinfunction "8_8") (pintype "passive"))
      (node (ref "B1") (pin "A8") (pinfunction "A8_A8") (pintype "bidirectional"))
    )
    (net (code "63") (name "Net-(ANALOG_SPARE-Pad9)") (class "Default")
      (node (ref "ANALOG_SPARE") (pin "9") (pinfunction "9_9") (pintype "passive"))
      (node (ref "B1") (pin "A7") (pinfunction "A7_A7") (pintype "bidirectional"))
    )
    (net (code "64") (name "Net-(ANALOG_SPARE-Pad10)") (class "Default")
      (node (ref "ANALOG_SPARE") (pin "10") (pinfunction "10_10") (pintype "passive"))
      (node (ref "B1") (pin "A6") (pinfunction "A6_A6") (pintype "bidirectional"))
    )
    (net (code "65") (name "Net-(B1-0(RX0))") (class "Default")
      (node (ref "B1") (pin "0") (pinfunction "0(RX0)_0") (pintype "bidirectional"))
      (node (ref "SERIAL_MEGA") (pin "2") (pinfunction "2_2") (pintype "passive"))
    )
    (net (code "66") (name "Net-(B1-1(TX0))") (class "Default")
      (node (ref "B1") (pin "1") (pinfunction "1(TX0)_1") (pintype "bidirectional"))
      (node (ref "SERIAL_MEGA") (pin "1") (pinfunction "1_1") (pintype "passive"))
    )
    (net (code "67") (name "Net-(B1-50{slash}MISO)") (class "Default")
      (node (ref "B1") (pin "50") (pinfunction "50/MISO_50") (pintype "bidirectional"))
      (node (ref "ULTRASONIC") (pin "2") (pinfunction "2_2") (pintype "passive"))
    )
    (net (code "68") (name "Net-(B1-51{slash}MOSI)") (class "Default")
      (node (ref "B1") (pin "51") (pinfunction "51/MOSI_51") (pintype "bidirectional"))
      (node (ref "DIGITAL_SPARE_MEGA1") (pin "2") (pinfunction "2_2") (pintype "passive"))
    )
    (net (code "69") (name "Net-(B1-52{slash}SCK)") (class "Default")
      (node (ref "B1") (pin "52") (pinfunction "52/SCK_52") (pintype "bidirectional"))
      (node (ref "ULTRASONIC") (pin "3") (pinfunction "3_3") (pintype "passive"))
    )
    (net (code "70") (name "Net-(B1-53{slash}~{CS})") (class "Default")
      (node (ref "B1") (pin "53") (pinfunction "53/~{CS}_53") (pintype "bidirectional"))
      (node (ref "DIGITAL_SPARE_MEGA1") (pin "1") (pinfunction "1_1") (pintype "passive"))
    )
    (net (code "71") (name "Net-(B1-Pad23)") (class "Default")
      (node (ref "B1") (pin "23") (pinfunction "23_23") (pintype "bidirectional"))
      (node (ref "ULTRASONIC1") (pin "3") (pinfunction "3_3") (pintype "passive"))
    )
    (net (code "72") (name "Net-(B1-Pad25)") (class "Default")
      (node (ref "B1") (pin "25") (pinfunction "25_25") (pintype "bidirectional"))
      (node (ref "ULTRASONIC1") (pin "2") (pinfunction "2_2") (pintype "passive"))
    )
    (net (code "73") (name "Net-(B1-Pad26)") (class "Default")
      (node (ref "B1") (pin "26") (pinfunction "26_26") (pintype "bidirectional"))
      (node (ref "JP1") (pin "1") (pinfunction "1_1") (pintype "passive"))
    )
    (net (code "74") (name "Net-(B1-Pad28)") (class "Default")
      (node (ref "B1") (pin "28") (pinfunction "28_28") (pintype "bidirectional"))
      (node (ref "JP1") (pin "2") (pinfunction "2_2") (pintype "passive"))
    )
    (net (code "75") (name "Net-(B1-Pad32)") (class "Default")
      (node (ref "B1") (pin "32") (pinfunction "32_32") (pintype "bidirectional"))
      (node (ref "JP3") (pin "1") (pinfunction "1_1") (pintype "passive"))
    )
    (net (code "76") (name "Net-(B1-Pad34)") (class "Default")
      (node (ref "B1") (pin "34") (pinfunction "34_34") (pintype "bidirectional"))
      (node (ref "JP3") (pin "2") (pinfunction "2_2") (pintype "passive"))
    )
    (net (code "77") (name "Net-(B1-Pad41)") (class "Default")
      (node (ref "B1") (pin "41") (pinfunction "41_41") (pintype "bidirectional"))
      (node (ref "DIGITAL_SPARE_MEGA1") (pin "7") (pinfunction "7_7") (pintype "passive"))
    )
    (net (code "78") (name "Net-(B1-Pad43)") (class "Default")
      (node (ref "B1") (pin "43") (pinfunction "43_43") (pintype "bidirectional"))
      (node (ref "DIGITAL_SPARE_MEGA1") (pin "6") (pinfunction "6_6") (pintype "passive"))
    )
    (net (code "79") (name "Net-(B1-Pad45)") (class "Default")
      (node (ref "B1") (pin "45") (pinfunction "45_45") (pintype "bidirectional"))
      (node (ref "DIGITAL_SPARE_MEGA1") (pin "5") (pinfunction "5_5") (pintype "passive"))
    )
    (net (code "80") (name "Net-(B1-Pad47)") (class "Default")
      (node (ref "B1") (pin "47") (pinfunction "47_47") (pintype "bidirectional"))
      (node (ref "DIGITAL_SPARE_MEGA1") (pin "4") (pinfunction "4_4") (pintype "passive"))
    )
    (net (code "81") (name "Net-(B1-Pad48)") (class "Default")
      (node (ref "B1") (pin "48") (pinfunction "48_48") (pintype "bidirectional"))
      (node (ref "JP3") (pin "3") (pinfunction "3_3") (pintype "passive"))
    )
    (net (code "82") (name "Net-(B1-Pad49)") (class "Default")
      (node (ref "B1") (pin "49") (pinfunction "49_49") (pintype "bidirectional"))
      (node (ref "DIGITAL_SPARE_MEGA1") (pin "3") (pinfunction "3_3") (pintype "passive"))
    )
    (net (code "83") (name "Net-(B1-PadA0)") (class "Default")
      (node (ref "B1") (pin "A0") (pinfunction "A0_A0") (pintype "bidirectional"))
      (node (ref "JP4") (pin "1") (pinfunction "1_1") (pintype "passive"))
    )
    (net (code "84") (name "Net-(B1-PadA1)") (class "Default")
      (node (ref "B1") (pin "A1") (pinfunction "A1_A1") (pintype "bidirectional"))
      (node (ref "JP4") (pin "2") (pinfunction "2_2") (pintype "passive"))
    )
    (net (code "85") (name "Net-(B1-PadAREF)") (class "Default")
      (node (ref "B1") (pin "AREF") (pinfunction "AREF_AREF") (pintype "bidirectional"))
      (node (ref "I2C") (pin "3") (pinfunction "3_3") (pintype "passive"))
    )
    (net (code "86") (name "Net-(B1-PadSCL)") (class "Default")
      (node (ref "B1") (pin "SCL") (pinfunction "SCL_SCL") (pintype "bidirectional"))
      (node (ref "I2C") (pin "1") (pinfunction "1_1") (pintype "passive"))
    )
    (net (code "87") (name "Net-(B1-PadSDA)") (class "Default")
      (node (ref "B1") (pin "SDA") (pinfunction "SDA_SDA") (pintype "bidirectional"))
      (node (ref "I2C") (pin "2") (pinfunction "2_2") (pintype "passive"))
    )
    (net (code "88") (name "Net-(D1-PadA)") (class "Default")
      (node (ref "D1") (pin "A") (pinfunction "A_A") (pintype "passive"))
      (node (ref "F4") (pin "2") (pinfunction "2_2") (pintype "passive"))
    )
    (net (code "89") (name "Net-(DIGITAL_SPARE_NANO-Pad1)") (class "Default")
      (node (ref "DIGITAL_SPARE_NANO") (pin "1") (pinfunction "1_1") (pintype "passive"))
      (node (ref "U$1") (pin "D8") (pinfunction "D8_D8") (pintype "bidirectional"))
    )
    (net (code "90") (name "Net-(DIGITAL_SPARE_NANO-Pad2)") (class "Default")
      (node (ref "DIGITAL_SPARE_NANO") (pin "2") (pinfunction "2_2") (pintype "passive"))
      (node (ref "U$1") (pin "D7") (pinfunction "D7_D7") (pintype "bidirectional"))
    )
    (net (code "91") (name "Net-(DIGITAL_SPARE_NANO-Pad3)") (class "Default")
      (node (ref "DIGITAL_SPARE_NANO") (pin "3") (pinfunction "3_3") (pintype "passive"))
      (node (ref "U$1") (pin "D6") (pinfunction "D6_D6") (pintype "bidirectional"))
    )
    (net (code "92") (name "Net-(IMU-Pad5)") (class "Default")
      (node (ref "IMU") (pin "5") (pinfunction "5_5") (pintype "passive"))
      (node (ref "U$1") (pin "A4") (pinfunction "A4_A4") (pintype "bidirectional"))
    )
    (net (code "93") (name "Net-(IMU-Pad6)") (class "Default")
      (node (ref "IMU") (pin "6") (pinfunction "6_6") (pintype "passive"))
      (node (ref "U$1") (pin "A5") (pinfunction "A5_A5") (pintype "bidirectional"))
    )
    (net (code "94") (name "Net-(LED1-PadA)") (class "Default")
      (node (ref "LED1") (pin "A") (pinfunction "A_A") (pintype "passive"))
      (node (ref "R1") (pin "2") (pinfunction "2_2") (pintype "passive"))
    )
    (net (code "95") (name "Net-(LED2-PadA)") (class "Default")
      (node (ref "LED2") (pin "A") (pinfunction "A_A") (pintype "passive"))
      (node (ref "R2") (pin "2") (pinfunction "2_2") (pintype "passive"))
    )
    (net (code "96") (name "Net-(LED3-PadA)") (class "Default")
      (node (ref "LED3") (pin "A") (pinfunction "A_A") (pintype "passive"))
      (node (ref "R22") (pin "2") (pinfunction "2_2") (pintype "passive"))
    )
    (net (code "97") (name "Net-(LED4-C)") (class "Default")
      (node (ref "2.33K") (pin "2") (pinfunction "2_2") (pintype "passive"))
      (node (ref "LED4") (pin "K") (pinfunction "C_K") (pintype "passive"))
    )
    (net (code "98") (name "Net-(LED5-PadA)") (class "Default")
      (node (ref "LED5") (pin "A") (pinfunction "A_A") (pintype "passive"))
      (node (ref "R3") (pin "2") (pinfunction "2_2") (pintype "passive"))
    )
    (net (code "99") (name "Net-(LED6-PadA)") (class "Default")
      (node (ref "LED6") (pin "A") (pinfunction "A_A") (pintype "passive"))
      (node (ref "R4") (pin "2") (pinfunction "2_2") (pintype "passive"))
    )
    (net (code "100") (name "Net-(LED7-PadA)") (class "Default")
      (node (ref "LED7") (pin "A") (pinfunction "A_A") (pintype "passive"))
      (node (ref "R5") (pin "2") (pinfunction "2_2") (pintype "passive"))
    )
    (net (code "101") (name "Net-(LED8-PadA)") (class "Default")
      (node (ref "LED8") (pin "A") (pinfunction "A_A") (pintype "passive"))
      (node (ref "R6") (pin "2") (pinfunction "2_2") (pintype "passive"))
    )
    (net (code "102") (name "Net-(LED9-PadA)") (class "Default")
      (node (ref "LED9") (pin "A") (pinfunction "A_A") (pintype "passive"))
      (node (ref "R7") (pin "2") (pinfunction "2_2") (pintype "passive"))
    )
    (net (code "103") (name "Net-(Q1-PadB)") (class "Default")
      (node (ref "Q1") (pin "B") (pinfunction "B_B") (pintype "passive"))
      (node (ref "R15") (pin "2") (pinfunction "2_2") (pintype "passive"))
    )
    (net (code "104") (name "Net-(Q2-PadB)") (class "Default")
      (node (ref "Q2") (pin "B") (pinfunction "B_B") (pintype "passive"))
      (node (ref "R16") (pin "2") (pinfunction "2_2") (pintype "passive"))
    )
    (net (code "105") (name "Net-(Q3-PadB)") (class "Default")
      (node (ref "Q3") (pin "B") (pinfunction "B_B") (pintype "passive"))
      (node (ref "R19") (pin "2") (pinfunction "2_2") (pintype "passive"))
    )
    (net (code "106") (name "Net-(Q4-PadB)") (class "Default")
      (node (ref "Q4") (pin "B") (pinfunction "B_B") (pintype "passive"))
      (node (ref "R18") (pin "2") (pinfunction "2_2") (pintype "passive"))
    )
    (net (code "107") (name "Net-(Q5-PadB)") (class "Default")
      (node (ref "Q5") (pin "B") (pinfunction "B_B") (pintype "passive"))
      (node (ref "R17") (pin "2") (pinfunction "2_2") (pintype "passive"))
    )
    (net (code "108") (name "Net-(Q6-PadB)") (class "Default")
      (node (ref "Q6") (pin "B") (pinfunction "B_B") (pintype "passive"))
      (node (ref "R20") (pin "2") (pinfunction "2_2") (pintype "passive"))
    )
    (net (code "109") (name "Net-(Q7-PadB)") (class "Default")
      (node (ref "Q7") (pin "B") (pinfunction "B_B") (pintype "passive"))
      (node (ref "R21") (pin "2") (pinfunction "2_2") (pintype "passive"))
    )
    (net (code "110") (name "Net-(SERIAL_NANO-Pad1)") (class "Default")
      (node (ref "SERIAL_NANO") (pin "1") (pinfunction "1_1") (pintype "passive"))
      (node (ref "U$1") (pin "RX1") (pinfunction "RX1_RX1") (pintype "bidirectional"))
    )
    (net (code "111") (name "Net-(SERIAL_NANO-Pad2)") (class "Default")
      (node (ref "SERIAL_NANO") (pin "2") (pinfunction "2_2") (pintype "passive"))
      (node (ref "U$1") (pin "TX0") (pinfunction "TX0_TX0") (pintype "bidirectional"))
    )
    (net (code "112") (name "Net-(STATE-C)") (class "Default")
      (node (ref "330") (pin "2") (pinfunction "2_2") (pintype "passive"))
      (node (ref "STATE") (pin "K") (pinfunction "C_K") (pintype "passive"))
    )
    (net (code "113") (name "Net-(U$1-PadD9)") (class "Default")
      (node (ref "U$1") (pin "D9") (pinfunction "D9_D9") (pintype "bidirectional"))
      (node (ref "ULTRASONIC3") (pin "3") (pinfunction "3_3") (pintype "passive"))
    )
    (net (code "114") (name "Net-(U$1-PadD10)") (class "Default")
      (node (ref "U$1") (pin "D10") (pinfunction "D10_D10") (pintype "bidirectional"))
      (node (ref "ULTRASONIC3") (pin "2") (pinfunction "2_2") (pintype "passive"))
    )
    (net (code "115") (name "Net-(U$1-PadD11)") (class "Default")
      (node (ref "U$1") (pin "D11") (pinfunction "D11_D11") (pintype "bidirectional"))
      (node (ref "ULTRASONIC2") (pin "3") (pinfunction "3_3") (pintype "passive"))
    )
    (net (code "116") (name "Net-(U$1-PadD12)") (class "Default")
      (node (ref "U$1") (pin "D12") (pinfunction "D12_D12") (pintype "bidirectional"))
      (node (ref "ULTRASONIC2") (pin "2") (pinfunction "2_2") (pintype "passive"))
    )
    (net (code "117") (name "PWM.A") (class "Default")
      (node (ref "B1") (pin "12") (pinfunction "12_12") (pintype "bidirectional"))
      (node (ref "DRIVER.1") (pin "2") (pinfunction "2_2") (pintype "passive"))
    )
    (net (code "118") (name "PWM.B") (class "Default")
      (node (ref "B1") (pin "11") (pinfunction "11_11") (pintype "bidirectional"))
      (node (ref "DRIVER.1") (pin "4") (pinfunction "4_4") (pintype "passive"))
    )
    (net (code "119") (name "PWM.C") (class "Default")
      (node (ref "B1") (pin "9") (pinfunction "9_9") (pintype "bidirectional"))
      (node (ref "DRIVER.2") (pin "2") (pinfunction "2_2") (pintype "passive"))
    )
    (net (code "120") (name "PWM.D") (class "Default")
      (node (ref "B1") (pin "10") (pinfunction "10_10") (pintype "bidirectional"))
      (node (ref "DRIVER.2") (pin "4") (pinfunction "4_4") (pintype "passive"))
    )
    (net (code "121") (name "PWM.E") (class "Default")
      (node (ref "B1") (pin "8") (pinfunction "8_8") (pintype "bidirectional"))
      (node (ref "DRIVER.3") (pin "2") (pinfunction "2_2") (pintype "passive"))
    )
    (net (code "122") (name "PWM.F") (class "Default")
      (node (ref "B1") (pin "7") (pinfunction "7_7") (pintype "bidirectional"))
      (node (ref "DRIVER.3") (pin "4") (pinfunction "4_4") (pintype "passive"))
    )
    (net (code "123") (name "PWM.G") (class "Default")
      (node (ref "B1") (pin "6") (pinfunction "6_6") (pintype "bidirectional"))
      (node (ref "DRIVER.4") (pin "2") (pinfunction "2_2") (pintype "passive"))
    )
    (net (code "124") (name "PWM.H") (class "Default")
      (node (ref "B1") (pin "4") (pinfunction "4_4") (pintype "bidirectional"))
      (node (ref "DRIVER.4") (pin "4") (pinfunction "4_4") (pintype "passive"))
    )
    (net (code "125") (name "RESET.MEGA") (class "Default")
      (node (ref "1K") (pin "1") (pinfunction "1_1") (pintype "passive"))
      (node (ref "B1") (pin "RESET") (pinfunction "~{RESET}_RESET") (pintype "bidirectional"))
      (node (ref "U$2") (pin "2") (pinfunction "2_2") (pintype "bidirectional"))
    )
    (net (code "126") (name "RX.BLUE") (class "Default")
      (node (ref "1.1K") (pin "1") (pinfunction "1_1") (pintype "passive"))
      (node (ref "2.32K") (pin "2") (pinfunction "2_2") (pintype "passive"))
      (node (ref "BLUETOOTH") (pin "2") (pinfunction "2_2") (pintype "passive"))
    )
    (net (code "127") (name "RX.NANO") (class "Default")
      (node (ref "B1") (pin "16") (pinfunction "16(TX2)_16") (pintype "bidirectional"))
      (node (ref "U$1") (pin "D5") (pinfunction "D5_D5") (pintype "bidirectional"))
    )
    (net (code "128") (name "STATE") (class "Default")
      (node (ref "B1") (pin "30") (pinfunction "30_30") (pintype "bidirectional"))
      (node (ref "BLUETOOTH") (pin "1") (pinfunction "1_1") (pintype "passive"))
      (node (ref "STATE") (pin "A") (pinfunction "A_A") (pintype "passive"))
    )
    (net (code "129") (name "TX.BLUE") (class "Default")
      (node (ref "B1") (pin "15") (pinfunction "15(RX3)_15") (pintype "bidirectional"))
      (node (ref "BLUETOOTH") (pin "3") (pinfunction "3_3") (pintype "passive"))
    )
    (net (code "130") (name "TX.MEGA") (class "Default")
      (node (ref "1.1K") (pin "2") (pinfunction "2_2") (pintype "passive"))
      (node (ref "B1") (pin "14") (pinfunction "14(TX3)_14") (pintype "bidirectional"))
    )
    (net (code "131") (name "TX.NANO") (class "Default")
      (node (ref "B1") (pin "17") (pinfunction "17(RX2)_17") (pintype "bidirectional"))
      (node (ref "U$1") (pin "D4") (pinfunction "D4_D4") (pintype "bidirectional"))
    )
    (net (code "132") (name "unconnected-(B1-Pad13)") (class "Default")
      (node (ref "B1") (pin "13") (pinfunction "13_13") (pintype "bidirectional"))
    )
    (net (code "133") (name "unconnected-(B1-Pad22)") (class "Default")
      (node (ref "B1") (pin "22") (pinfunction "22_22") (pintype "bidirectional"))
    )
    (net (code "134") (name "unconnected-(B1-PadIOREF)") (class "Default")
      (node (ref "B1") (pin "IOREF") (pinfunction "IOREF_IOREF") (pintype "bidirectional"))
    )
    (net (code "135") (name "unconnected-(B1-PadVIN)") (class "Default")
      (node (ref "B1") (pin "VIN") (pinfunction "VIN_VIN") (pintype "bidirectional"))
    )
    (net (code "136") (name "unconnected-(ENCODER.A-Pad3)") (class "Default")
      (node (ref "ENCODER.A") (pin "3") (pinfunction "3_3") (pintype "passive"))
    )
    (net (code "137") (name "unconnected-(ENCODER.A1-Pad3)") (class "Default")
      (node (ref "ENCODER.A1") (pin "3") (pinfunction "3_3") (pintype "passive"))
    )
    (net (code "138") (name "unconnected-(ENCODER.C-Pad3)") (class "Default")
      (node (ref "ENCODER.C") (pin "3") (pinfunction "3_3") (pintype "passive"))
    )
    (net (code "139") (name "unconnected-(ENCODER.C1-Pad3)") (class "Default")
      (node (ref "ENCODER.C1") (pin "3") (pinfunction "3_3") (pintype "passive"))
    )
    (net (code "140") (name "unconnected-(ENCODER.C2-Pad3)") (class "Default")
      (node (ref "ENCODER.C2") (pin "3") (pinfunction "3_3") (pintype "passive"))
    )
    (net (code "141") (name "unconnected-(ENCODER.C3-Pad3)") (class "Default")
      (node (ref "ENCODER.C3") (pin "3") (pinfunction "3_3") (pintype "passive"))
    )
    (net (code "142") (name "unconnected-(IC1A-A-Pad15)") (class "Default")
      (node (ref "IC1") (pin "15") (pinfunction "A_15") (pintype "input"))
    )
    (net (code "143") (name "unconnected-(IC1A-B-Pad1)") (class "Default")
      (node (ref "IC1") (pin "1") (pinfunction "B_1") (pintype "input"))
    )
    (net (code "144") (name "unconnected-(IC1A-BO-Pad13)") (class "Default")
      (node (ref "IC1") (pin "13") (pinfunction "BO_13") (pintype "output"))
    )
    (net (code "145") (name "unconnected-(IC1A-C-Pad10)") (class "Default")
      (node (ref "IC1") (pin "10") (pinfunction "C_10") (pintype "input"))
    )
    (net (code "146") (name "unconnected-(IC1A-D-Pad9)") (class "Default")
      (node (ref "IC1") (pin "9") (pinfunction "D_9") (pintype "input"))
    )
    (net (code "147") (name "unconnected-(IC1A-QA-Pad3)") (class "Default")
      (node (ref "IC1") (pin "3") (pinfunction "QA_3") (pintype "output"))
    )
    (net (code "148") (name "unconnected-(IC1A-QB-Pad2)") (class "Default")
      (node (ref "IC1") (pin "2") (pinfunction "QB_2") (pintype "output"))
    )
    (net (code "149") (name "unconnected-(IC1A-QC-Pad6)") (class "Default")
      (node (ref "IC1") (pin "6") (pinfunction "QC_6") (pintype "output"))
    )
    (net (code "150") (name "unconnected-(IC1A-QD-Pad7)") (class "Default")
      (node (ref "IC1") (pin "7") (pinfunction "QD_7") (pintype "output"))
    )
    (net (code "151") (name "unconnected-(IC2A-A-Pad15)") (class "Default")
      (node (ref "IC2") (pin "15") (pinfunction "A_15") (pintype "input"))
    )
    (net (code "152") (name "unconnected-(IC2A-B-Pad1)") (class "Default")
      (node (ref "IC2") (pin "1") (pinfunction "B_1") (pintype "input"))
    )
    (net (code "153") (name "unconnected-(IC2A-BO-Pad13)") (class "Default")
      (node (ref "IC2") (pin "13") (pinfunction "BO_13") (pintype "output"))
    )
    (net (code "154") (name "unconnected-(IC2A-C-Pad10)") (class "Default")
      (node (ref "IC2") (pin "10") (pinfunction "C_10") (pintype "input"))
    )
    (net (code "155") (name "unconnected-(IC2A-D-Pad9)") (class "Default")
      (node (ref "IC2") (pin "9") (pinfunction "D_9") (pintype "input"))
    )
    (net (code "156") (name "unconnected-(IC2A-QA-Pad3)") (class "Default")
      (node (ref "IC2") (pin "3") (pinfunction "QA_3") (pintype "output"))
    )
    (net (code "157") (name "unconnected-(IC2A-QB-Pad2)") (class "Default")
      (node (ref "IC2") (pin "2") (pinfunction "QB_2") (pintype "output"))
    )
    (net (code "158") (name "unconnected-(IC2A-QC-Pad6)") (class "Default")
      (node (ref "IC2") (pin "6") (pinfunction "QC_6") (pintype "output"))
    )
    (net (code "159") (name "unconnected-(IC2A-QD-Pad7)") (class "Default")
      (node (ref "IC2") (pin "7") (pinfunction "QD_7") (pintype "output"))
    )
    (net (code "160") (name "unconnected-(IC3A-A-Pad15)") (class "Default")
      (node (ref "IC3") (pin "15") (pinfunction "A_15") (pintype "input"))
    )
    (net (code "161") (name "unconnected-(IC3A-B-Pad1)") (class "Default")
      (node (ref "IC3") (pin "1") (pinfunction "B_1") (pintype "input"))
    )
    (net (code "162") (name "unconnected-(IC3A-BO-Pad13)") (class "Default")
      (node (ref "IC3") (pin "13") (pinfunction "BO_13") (pintype "output"))
    )
    (net (code "163") (name "unconnected-(IC3A-C-Pad10)") (class "Default")
      (node (ref "IC3") (pin "10") (pinfunction "C_10") (pintype "input"))
    )
    (net (code "164") (name "unconnected-(IC3A-D-Pad9)") (class "Default")
      (node (ref "IC3") (pin "9") (pinfunction "D_9") (pintype "input"))
    )
    (net (code "165") (name "unconnected-(IC3A-QA-Pad3)") (class "Default")
      (node (ref "IC3") (pin "3") (pinfunction "QA_3") (pintype "output"))
    )
    (net (code "166") (name "unconnected-(IC3A-QB-Pad2)") (class "Default")
      (node (ref "IC3") (pin "2") (pinfunction "QB_2") (pintype "output"))
    )
    (net (code "167") (name "unconnected-(IC3A-QC-Pad6)") (class "Default")
      (node (ref "IC3") (pin "6") (pinfunction "QC_6") (pintype "output"))
    )
    (net (code "168") (name "unconnected-(IC3A-QD-Pad7)") (class "Default")
      (node (ref "IC3") (pin "7") (pinfunction "QD_7") (pintype "output"))
    )
    (net (code "169") (name "unconnected-(IC4A-A-Pad15)") (class "Default")
      (node (ref "IC4") (pin "15") (pinfunction "A_15") (pintype "input"))
    )
    (net (code "170") (name "unconnected-(IC4A-B-Pad1)") (class "Default")
      (node (ref "IC4") (pin "1") (pinfunction "B_1") (pintype "input"))
    )
    (net (code "171") (name "unconnected-(IC4A-BO-Pad13)") (class "Default")
      (node (ref "IC4") (pin "13") (pinfunction "BO_13") (pintype "output"))
    )
    (net (code "172") (name "unconnected-(IC4A-C-Pad10)") (class "Default")
      (node (ref "IC4") (pin "10") (pinfunction "C_10") (pintype "input"))
    )
    (net (code "173") (name "unconnected-(IC4A-D-Pad9)") (class "Default")
      (node (ref "IC4") (pin "9") (pinfunction "D_9") (pintype "input"))
    )
    (net (code "174") (name "unconnected-(IC4A-QA-Pad3)") (class "Default")
      (node (ref "IC4") (pin "3") (pinfunction "QA_3") (pintype "output"))
    )
    (net (code "175") (name "unconnected-(IC4A-QB-Pad2)") (class "Default")
      (node (ref "IC4") (pin "2") (pinfunction "QB_2") (pintype "output"))
    )
    (net (code "176") (name "unconnected-(IC4A-QC-Pad6)") (class "Default")
      (node (ref "IC4") (pin "6") (pinfunction "QC_6") (pintype "output"))
    )
    (net (code "177") (name "unconnected-(IC4A-QD-Pad7)") (class "Default")
      (node (ref "IC4") (pin "7") (pinfunction "QD_7") (pintype "output"))
    )
    (net (code "178") (name "unconnected-(IMU-Pad2)") (class "Default")
      (node (ref "IMU") (pin "2") (pinfunction "2_2") (pintype "passive"))
    )
    (net (code "179") (name "unconnected-(IMU-Pad3)") (class "Default")
      (node (ref "IMU") (pin "3") (pinfunction "3_3") (pintype "passive"))
    )
    (net (code "180") (name "unconnected-(IMU-Pad4)") (class "Default")
      (node (ref "IMU") (pin "4") (pinfunction "4_4") (pintype "passive"))
    )
    (net (code "181") (name "unconnected-(U$1-PadAREF)") (class "Default")
      (node (ref "U$1") (pin "AREF") (pinfunction "AREF_AREF") (pintype "bidirectional"))
    )
    (net (code "182") (name "unconnected-(U$1-PadD13)") (class "Default")
      (node (ref "U$1") (pin "D13") (pinfunction "D13_D13") (pintype "bidirectional"))
    )
    (net (code "183") (name "unconnected-(U$1-PadRST)") (class "Default")
      (node (ref "U$1") (pin "RST") (pinfunction "RST_RST") (pintype "bidirectional"))
    )
    (net (code "184") (name "unconnected-(U$1-PadRST1)") (class "Default")
      (node (ref "U$1") (pin "RST1") (pinfunction "RST1_RST1") (pintype "bidirectional"))
    )
  )
)
